# schematic_v1.net
KiCad netlist of a schematic drawn in EAGLE
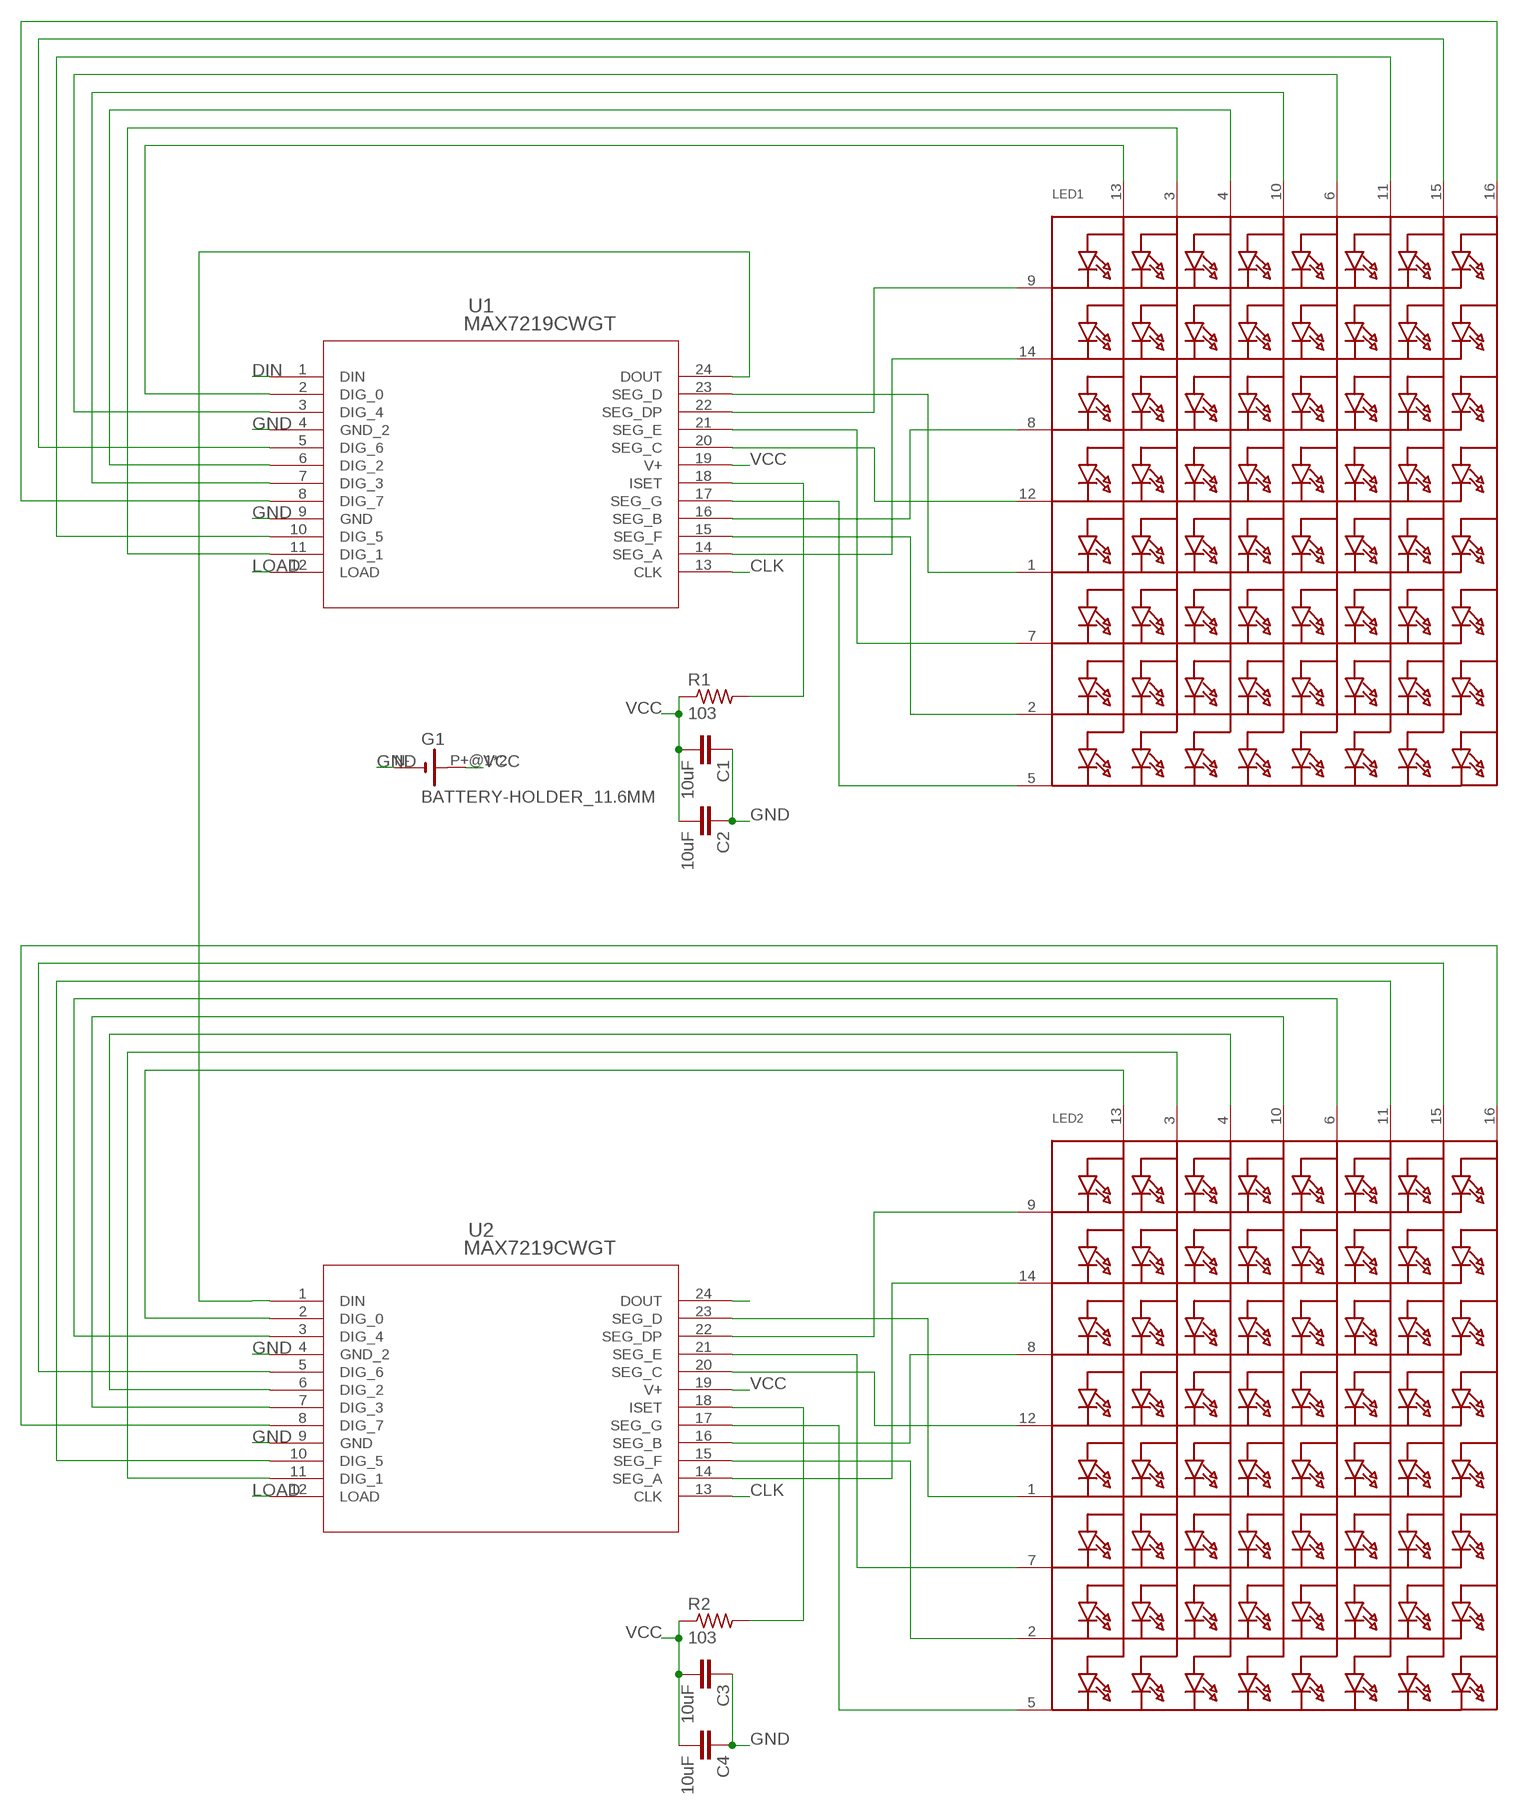
[diagram p0: schematic, sheet 1]

(export (version "E")
  (design (tool "Eeschema 10.0.6"))
  (components
    (comp (ref "C1")
      (value "10uF")
      (footprint "eagle-import:0805")
      (libsource (lib "eagle-import") (part "10UF-0805-10V-10%"))
    )
    (comp (ref "C2")
      (value "10uF")
      (footprint "eagle-import:0805")
      (libsource (lib "eagle-import") (part "10UF-0805-10V-10%"))
    )
    (comp (ref "C3")
      (value "10uF")
      (footprint "eagle-import:0805")
      (libsource (lib "eagle-import") (part "10UF-0805-10V-10%"))
    )
    (comp (ref "C4")
      (value "10uF")
      (footprint "eagle-import:0805")
      (libsource (lib "eagle-import") (part "10UF-0805-10V-10%"))
    )
    (comp (ref "G1")
      (value "BATTERY-HOLDER_11.6MM")
      (footprint "eagle-import:CELL_RETAINER_11.6MM")
      (fields (field (name "MF") "KEYSTONE") (field (name "MPN") "2997"))
      (libsource (lib "eagle-import") (part "BATTERY-HOLDER_11.6MM"))
    )
    (comp (ref "LED1")
      (value "SEGMENT_8X8_ROWCATHODEBL-M15")
      (footprint "eagle-import:SEGMENT_BL-M15A881")
      (libsource (lib "eagle-import") (part "SEGMENT_8X8_ROWCATHODEBL-M15"))
    )
    (comp (ref "LED2")
      (value "SEGMENT_8X8_ROWCATHODEBL-M15")
      (footprint "eagle-import:SEGMENT_BL-M15A881")
      (libsource (lib "eagle-import") (part "SEGMENT_8X8_ROWCATHODEBL-M15"))
    )
    (comp (ref "R1")
      (value "103")
      (footprint "eagle-import:M0805")
      (libsource (lib "eagle-import") (part "R-US_M0805"))
    )
    (comp (ref "R2")
      (value "103")
      (footprint "eagle-import:M0805")
      (libsource (lib "eagle-import") (part "R-US_M0805"))
    )
    (comp (ref "U1")
      (value "MAX7219CWGT")
      (footprint "eagle-import:21-0042B_24")
      (fields (field (name "MANUFACTURER_PART_NUMBER") "max7219cwg+t"))
      (libsource (lib "eagle-import") (part "MAX7219CWGT"))
    )
    (comp (ref "U2")
      (value "MAX7219CWGT")
      (footprint "eagle-import:21-0042B_24")
      (fields (field (name "MANUFACTURER_PART_NUMBER") "max7219cwg+t"))
      (libsource (lib "eagle-import") (part "MAX7219CWGT"))
    )
  )
  (nets
    (net (code "1") (name "/CLK") (class "Default")
      (node (ref "U1") (pin "13") (pinfunction "CLK_13") (pintype "input"))
      (node (ref "U2") (pin "13") (pinfunction "CLK_13") (pintype "input"))
    )
    (net (code "2") (name "/DIN") (class "Default")
      (node (ref "U1") (pin "1") (pinfunction "DIN_1") (pintype "input"))
    )
    (net (code "3") (name "/GND") (class "Default")
      (node (ref "C1") (pin "1") (pinfunction "1_1") (pintype "passive"))
      (node (ref "C2") (pin "1") (pinfunction "1_1") (pintype "passive"))
      (node (ref "C3") (pin "1") (pinfunction "1_1") (pintype "passive"))
      (node (ref "C4") (pin "1") (pinfunction "1_1") (pintype "passive"))
      (node (ref "G1") (pin "N-") (pinfunction "-_N-") (pintype "passive"))
      (node (ref "U1") (pin "4") (pinfunction "GND_2_4") (pintype "power_in"))
      (node (ref "U1") (pin "9") (pinfunction "GND_9") (pintype "power_in"))
      (node (ref "U2") (pin "4") (pinfunction "GND_2_4") (pintype "power_in"))
      (node (ref "U2") (pin "9") (pinfunction "GND_9") (pintype "power_in"))
    )
    (net (code "4") (name "/LOAD") (class "Default")
      (node (ref "U1") (pin "12") (pinfunction "LOAD_12") (pintype "input"))
      (node (ref "U2") (pin "12") (pinfunction "LOAD_12") (pintype "input"))
    )
    (net (code "5") (name "/VCC") (class "Default")
      (node (ref "C1") (pin "2") (pinfunction "2_2") (pintype "passive"))
      (node (ref "C2") (pin "2") (pinfunction "2_2") (pintype "passive"))
      (node (ref "C3") (pin "2") (pinfunction "2_2") (pintype "passive"))
      (node (ref "C4") (pin "2") (pinfunction "2_2") (pintype "passive"))
      (node (ref "G1") (pin "P+@1") (pinfunction "+_P+@1") (pintype "passive"))
      (node (ref "G1") (pin "P+@2") (pinfunction "+_P+@2") (pintype "passive"))
      (node (ref "R1") (pin "1") (pinfunction "1_1") (pintype "passive"))
      (node (ref "R2") (pin "1") (pinfunction "1_1") (pintype "passive"))
      (node (ref "U1") (pin "19") (pinfunction "V+_19") (pintype "power_in"))
      (node (ref "U2") (pin "19") (pinfunction "V+_19") (pintype "power_in"))
    )
    (net (code "6") (name "Net-(LED1-A1)") (class "Default")
      (node (ref "LED1") (pin "13") (pinfunction "A1_13") (pintype "bidirectional"))
      (node (ref "U1") (pin "2") (pinfunction "DIG_0_2") (pintype "passive"))
    )
    (net (code "7") (name "Net-(LED1-A2)") (class "Default")
      (node (ref "LED1") (pin "3") (pinfunction "A2_3") (pintype "bidirectional"))
      (node (ref "U1") (pin "11") (pinfunction "DIG_1_11") (pintype "passive"))
    )
    (net (code "8") (name "Net-(LED1-A3)") (class "Default")
      (node (ref "LED1") (pin "4") (pinfunction "A3_4") (pintype "bidirectional"))
      (node (ref "U1") (pin "6") (pinfunction "DIG_2_6") (pintype "passive"))
    )
    (net (code "9") (name "Net-(LED1-A4)") (class "Default")
      (node (ref "LED1") (pin "10") (pinfunction "A4_10") (pintype "bidirectional"))
      (node (ref "U1") (pin "7") (pinfunction "DIG_3_7") (pintype "passive"))
    )
    (net (code "10") (name "Net-(LED1-A5)") (class "Default")
      (node (ref "LED1") (pin "6") (pinfunction "A5_6") (pintype "bidirectional"))
      (node (ref "U1") (pin "3") (pinfunction "DIG_4_3") (pintype "passive"))
    )
    (net (code "11") (name "Net-(LED1-A6)") (class "Default")
      (node (ref "LED1") (pin "11") (pinfunction "A6_11") (pintype "bidirectional"))
      (node (ref "U1") (pin "10") (pinfunction "DIG_5_10") (pintype "passive"))
    )
    (net (code "12") (name "Net-(LED1-A7)") (class "Default")
      (node (ref "LED1") (pin "15") (pinfunction "A7_15") (pintype "bidirectional"))
      (node (ref "U1") (pin "5") (pinfunction "DIG_6_5") (pintype "passive"))
    )
    (net (code "13") (name "Net-(LED1-A8)") (class "Default")
      (node (ref "LED1") (pin "16") (pinfunction "A8_16") (pintype "bidirectional"))
      (node (ref "U1") (pin "8") (pinfunction "DIG_7_8") (pintype "passive"))
    )
    (net (code "14") (name "Net-(LED1-K1)") (class "Default")
      (node (ref "LED1") (pin "9") (pinfunction "K1_9") (pintype "bidirectional"))
      (node (ref "U1") (pin "22") (pinfunction "SEG_DP_22") (pintype "passive"))
    )
    (net (code "15") (name "Net-(LED1-K2)") (class "Default")
      (node (ref "LED1") (pin "14") (pinfunction "K2_14") (pintype "bidirectional"))
      (node (ref "U1") (pin "14") (pinfunction "SEG_A_14") (pintype "passive"))
    )
    (net (code "16") (name "Net-(LED1-K3)") (class "Default")
      (node (ref "LED1") (pin "8") (pinfunction "K3_8") (pintype "bidirectional"))
      (node (ref "U1") (pin "16") (pinfunction "SEG_B_16") (pintype "passive"))
    )
    (net (code "17") (name "Net-(LED1-K4)") (class "Default")
      (node (ref "LED1") (pin "12") (pinfunction "K4_12") (pintype "bidirectional"))
      (node (ref "U1") (pin "20") (pinfunction "SEG_C_20") (pintype "passive"))
    )
    (net (code "18") (name "Net-(LED1-K5)") (class "Default")
      (node (ref "LED1") (pin "1") (pinfunction "K5_1") (pintype "bidirectional"))
      (node (ref "U1") (pin "23") (pinfunction "SEG_D_23") (pintype "passive"))
    )
    (net (code "19") (name "Net-(LED1-K6)") (class "Default")
      (node (ref "LED1") (pin "7") (pinfunction "K6_7") (pintype "bidirectional"))
      (node (ref "U1") (pin "21") (pinfunction "SEG_E_21") (pintype "passive"))
    )
    (net (code "20") (name "Net-(LED1-K7)") (class "Default")
      (node (ref "LED1") (pin "2") (pinfunction "K7_2") (pintype "bidirectional"))
      (node (ref "U1") (pin "15") (pinfunction "SEG_F_15") (pintype "passive"))
    )
    (net (code "21") (name "Net-(LED1-K8)") (class "Default")
      (node (ref "LED1") (pin "5") (pinfunction "K8_5") (pintype "bidirectional"))
      (node (ref "U1") (pin "17") (pinfunction "SEG_G_17") (pintype "passive"))
    )
    (net (code "22") (name "Net-(LED2-A1)") (class "Default")
      (node (ref "LED2") (pin "13") (pinfunction "A1_13") (pintype "bidirectional"))
      (node (ref "U2") (pin "2") (pinfunction "DIG_0_2") (pintype "passive"))
    )
    (net (code "23") (name "Net-(LED2-A2)") (class "Default")
      (node (ref "LED2") (pin "3") (pinfunction "A2_3") (pintype "bidirectional"))
      (node (ref "U2") (pin "11") (pinfunction "DIG_1_11") (pintype "passive"))
    )
    (net (code "24") (name "Net-(LED2-A3)") (class "Default")
      (node (ref "LED2") (pin "4") (pinfunction "A3_4") (pintype "bidirectional"))
      (node (ref "U2") (pin "6") (pinfunction "DIG_2_6") (pintype "passive"))
    )
    (net (code "25") (name "Net-(LED2-A4)") (class "Default")
      (node (ref "LED2") (pin "10") (pinfunction "A4_10") (pintype "bidirectional"))
      (node (ref "U2") (pin "7") (pinfunction "DIG_3_7") (pintype "passive"))
    )
    (net (code "26") (name "Net-(LED2-A5)") (class "Default")
      (node (ref "LED2") (pin "6") (pinfunction "A5_6") (pintype "bidirectional"))
      (node (ref "U2") (pin "3") (pinfunction "DIG_4_3") (pintype "passive"))
    )
    (net (code "27") (name "Net-(LED2-A6)") (class "Default")
      (node (ref "LED2") (pin "11") (pinfunction "A6_11") (pintype "bidirectional"))
      (node (ref "U2") (pin "10") (pinfunction "DIG_5_10") (pintype "passive"))
    )
    (net (code "28") (name "Net-(LED2-A7)") (class "Default")
      (node (ref "LED2") (pin "15") (pinfunction "A7_15") (pintype "bidirectional"))
      (node (ref "U2") (pin "5") (pinfunction "DIG_6_5") (pintype "passive"))
    )
    (net (code "29") (name "Net-(LED2-A8)") (class "Default")
      (node (ref "LED2") (pin "16") (pinfunction "A8_16") (pintype "bidirectional"))
      (node (ref "U2") (pin "8") (pinfunction "DIG_7_8") (pintype "passive"))
    )
    (net (code "30") (name "Net-(LED2-K1)") (class "Default")
      (node (ref "LED2") (pin "9") (pinfunction "K1_9") (pintype "bidirectional"))
      (node (ref "U2") (pin "22") (pinfunction "SEG_DP_22") (pintype "passive"))
    )
    (net (code "31") (name "Net-(LED2-K2)") (class "Default")
      (node (ref "LED2") (pin "14") (pinfunction "K2_14") (pintype "bidirectional"))
      (node (ref "U2") (pin "14") (pinfunction "SEG_A_14") (pintype "passive"))
    )
    (net (code "32") (name "Net-(LED2-K3)") (class "Default")
      (node (ref "LED2") (pin "8") (pinfunction "K3_8") (pintype "bidirectional"))
      (node (ref "U2") (pin "16") (pinfunction "SEG_B_16") (pintype "passive"))
    )
    (net (code "33") (name "Net-(LED2-K4)") (class "Default")
      (node (ref "LED2") (pin "12") (pinfunction "K4_12") (pintype "bidirectional"))
      (node (ref "U2") (pin "20") (pinfunction "SEG_C_20") (pintype "passive"))
    )
    (net (code "34") (name "Net-(LED2-K5)") (class "Default")
      (node (ref "LED2") (pin "1") (pinfunction "K5_1") (pintype "bidirectional"))
      (node (ref "U2") (pin "23") (pinfunction "SEG_D_23") (pintype "passive"))
    )
    (net (code "35") (name "Net-(LED2-K6)") (class "Default")
      (node (ref "LED2") (pin "7") (pinfunction "K6_7") (pintype "bidirectional"))
      (node (ref "U2") (pin "21") (pinfunction "SEG_E_21") (pintype "passive"))
    )
    (net (code "36") (name "Net-(LED2-K7)") (class "Default")
      (node (ref "LED2") (pin "2") (pinfunction "K7_2") (pintype "bidirectional"))
      (node (ref "U2") (pin "15") (pinfunction "SEG_F_15") (pintype "passive"))
    )
    (net (code "37") (name "Net-(LED2-K8)") (class "Default")
      (node (ref "LED2") (pin "5") (pinfunction "K8_5") (pintype "bidirectional"))
      (node (ref "U2") (pin "17") (pinfunction "SEG_G_17") (pintype "passive"))
    )
    (net (code "38") (name "Net-(U1-DOUT)") (class "Default")
      (node (ref "U1") (pin "24") (pinfunction "DOUT_24") (pintype "output"))
      (node (ref "U2") (pin "1") (pinfunction "DIN_1") (pintype "input"))
    )
    (net (code "39") (name "Net-(U1-ISET)") (class "Default")
      (node (ref "R1") (pin "2") (pinfunction "2_2") (pintype "passive"))
      (node (ref "U1") (pin "18") (pinfunction "ISET_18") (pintype "passive"))
    )
    (net (code "40") (name "Net-(U2-ISET)") (class "Default")
      (node (ref "R2") (pin "2") (pinfunction "2_2") (pintype "passive"))
      (node (ref "U2") (pin "18") (pinfunction "ISET_18") (pintype "passive"))
    )
    (net (code "41") (name "unconnected-(U2-DOUT-Pad24)") (class "Default")
      (node (ref "U2") (pin "24") (pinfunction "DOUT_24") (pintype "output"))
    )
  )
)
